# VCO_OUT_channel.net
KiCad netlist of a schematic drawn in Altium Designer
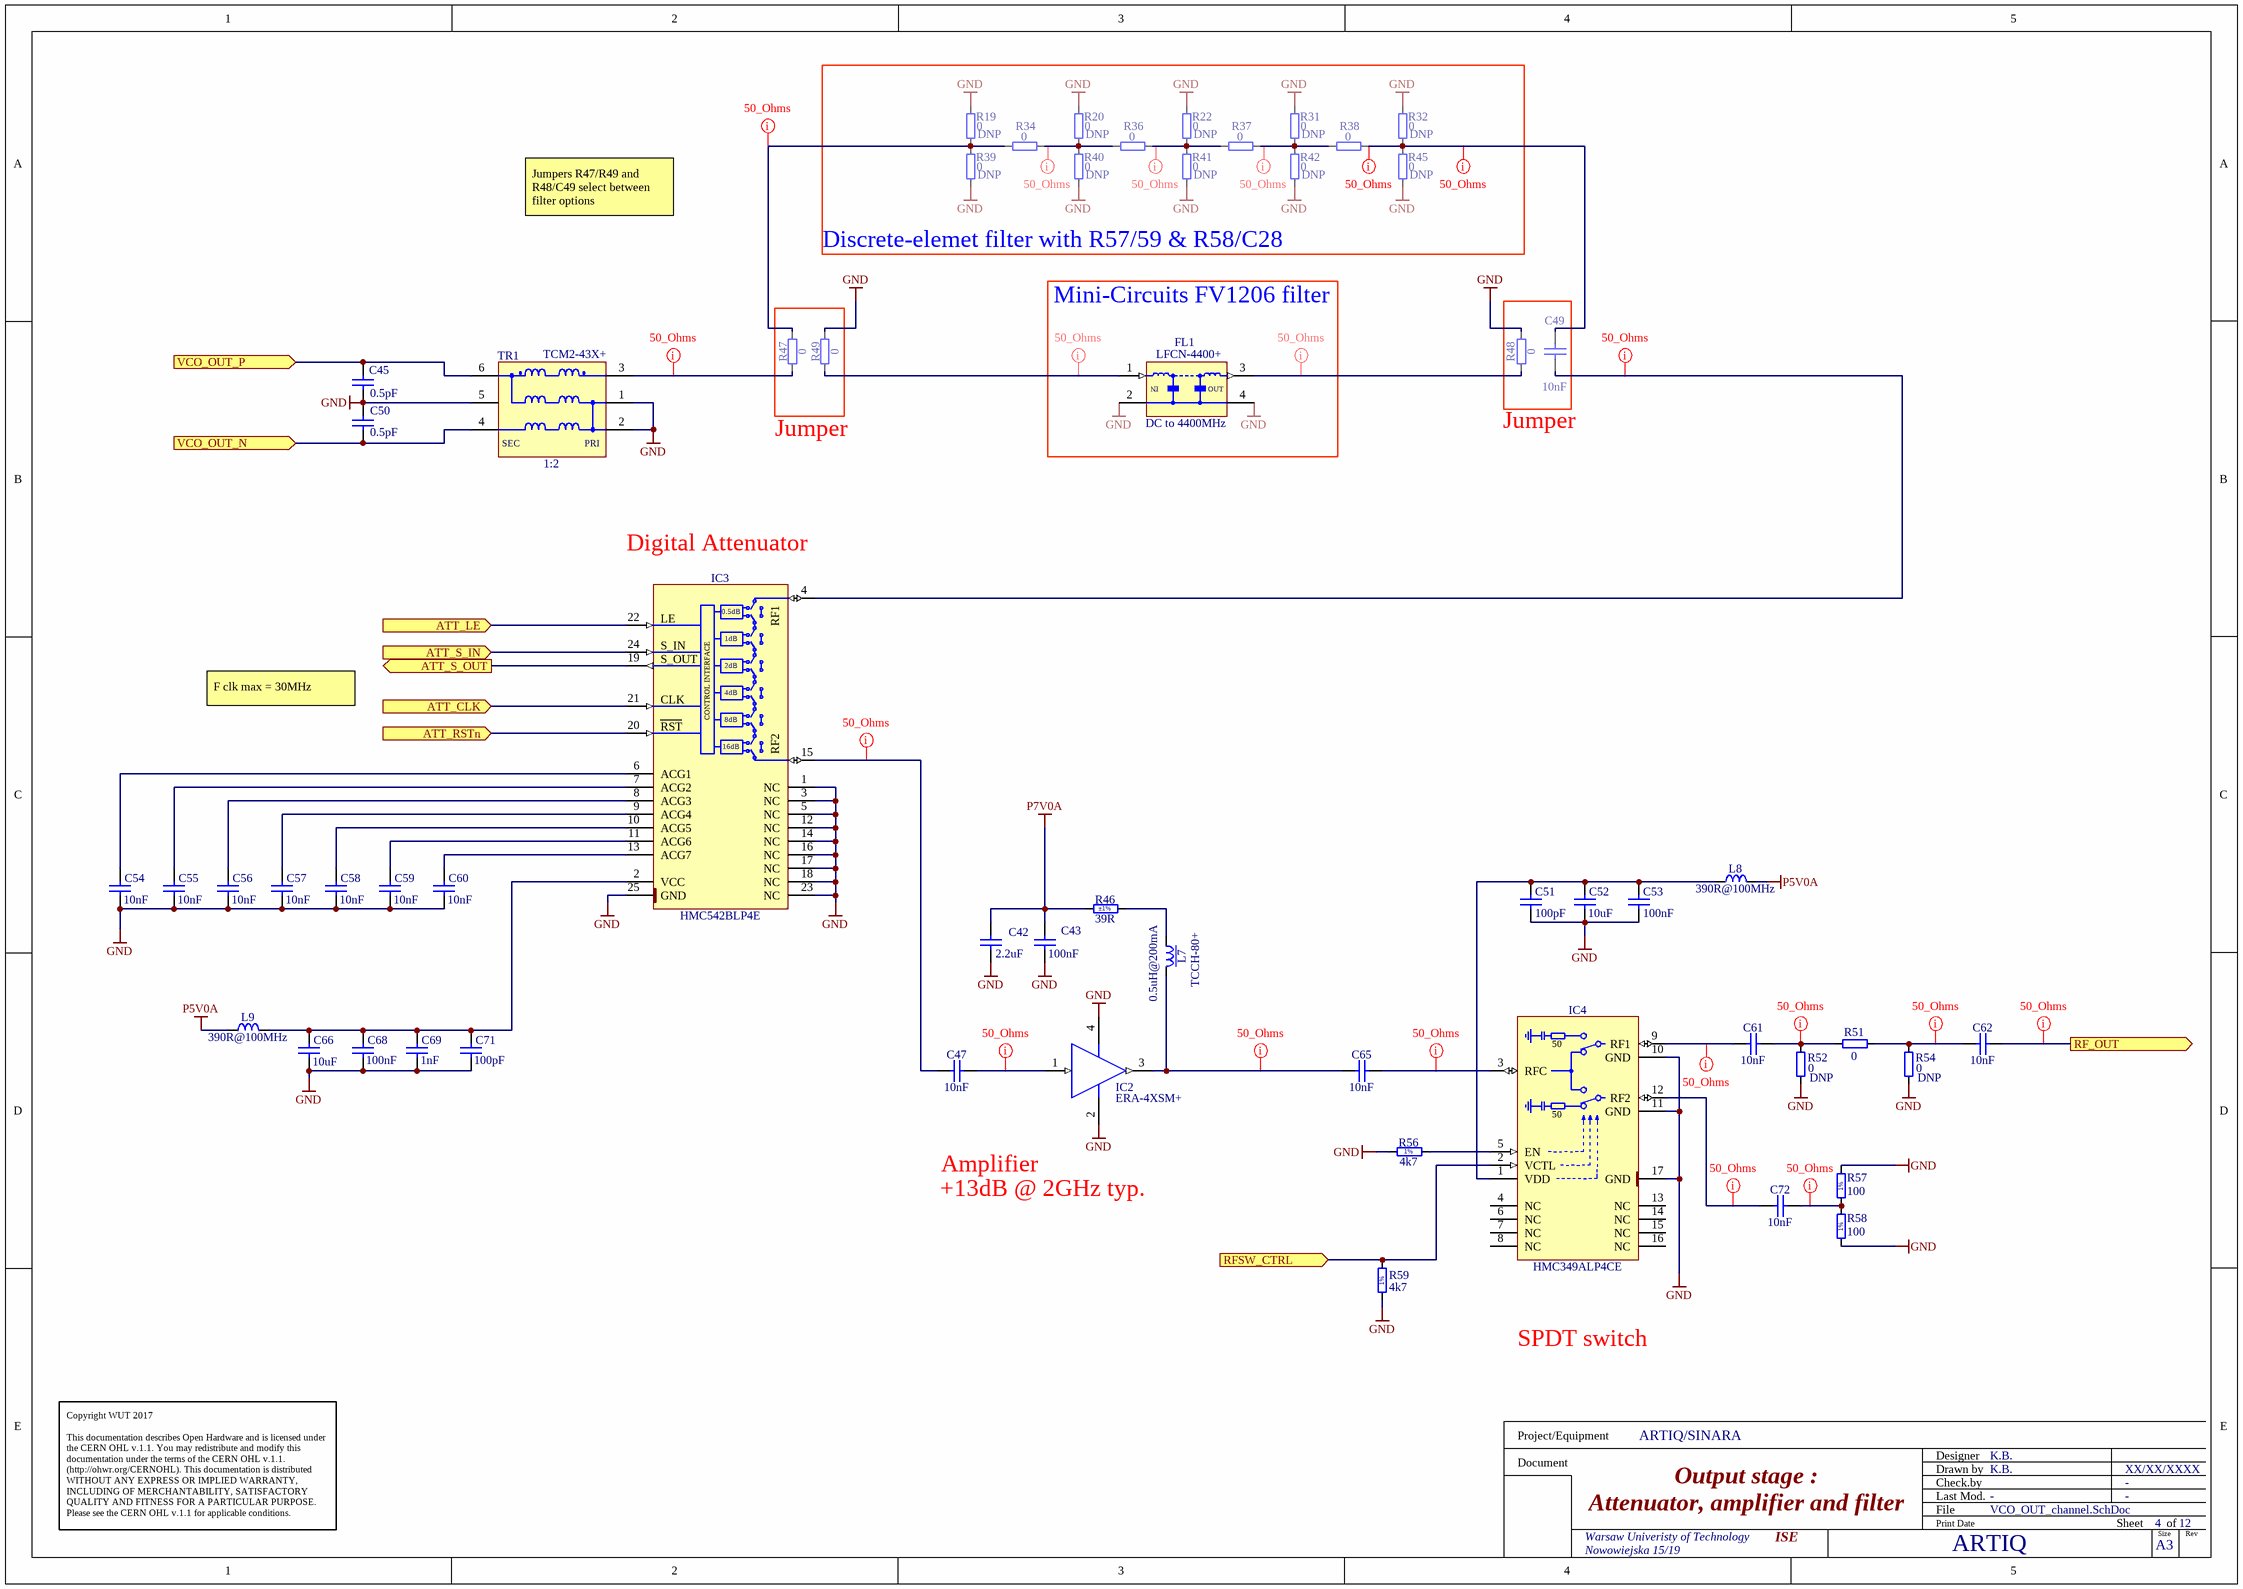
[diagram p0: VCO_OUT_channel.SchDoc]

(export (version "E")
  (design (tool "Eeschema 10.0.6"))
  (components
    (comp (ref "C42")
      (value "2.2uF")
      (footprint "CAPC2012X140N")
      (description "Non-polarised capacitor")
      (fields
        (field (name "PART NUMBER") "CC0805_2U2F_25V_20%_X7R")
        (field (name "VOLTAGE") "25V")
        (field (name "AUTHOR") "CERN DEM JLC")
      )
      (libsource (lib "Capacitors") (part "Capacitor - non polarized"))
    )
    (comp (ref "C43")
      (value "100nF")
      (footprint "CAPC1005X55N")
      (description "Non-polarised capacitor")
      (fields
        (field (name "PART NUMBER") "CC0402_100NF_16V_10%_X7R")
        (field (name "VOLTAGE") "16V")
        (field (name "AUTHOR") "CERN DEM JLC")
      )
      (libsource (lib "Capacitors") (part "Capacitor - non polarized"))
    )
    (comp (ref "C45")
      (value "0.5pF")
      (footprint "CAPC0402(1005)60_M")
      (description "CAP 0.5pF 10V ±0.1pF 0402 (1005 Metric) Thickness 0.6mm SMD")
      (fields (field (name "TOLERANCE") "Â±0.1pF"))
      (libsource (lib "Altium Content Vault") (part "CMP-1034-00013-1"))
    )
    (comp (ref "C47")
      (value "10nF")
      (footprint "CAPC1005X55N")
      (description "Non-polarised capacitor")
      (fields
        (field (name "PART NUMBER") "CC0402_10NF_16V_10%_X7R")
        (field (name "VOLTAGE") "16V")
        (field (name "AUTHOR") "CERN DEM JLC")
      )
      (libsource (lib "Capacitors") (part "Capacitor - non polarized"))
    )
    (comp (ref "C49")
      (value "10nF")
      (footprint "CAPC1005X55N")
      (description "Non-polarised capacitor")
      (fields
        (field (name "PART NUMBER") "CC0402_10NF_16V_10%_X7R")
        (field (name "VOLTAGE") "16V")
        (field (name "AUTHOR") "CERN DEM JLC")
      )
      (libsource (lib "Capacitors") (part "Capacitor - non polarized"))
    )
    (comp (ref "C50")
      (value "0.5pF")
      (footprint "CAPC0402(1005)60_M")
      (description "CAP 0.5pF 10V ±0.1pF 0402 (1005 Metric) Thickness 0.6mm SMD")
      (fields (field (name "TOLERANCE") "Â±0.1pF"))
      (libsource (lib "Altium Content Vault") (part "CMP-1034-00013-1"))
    )
    (comp (ref "C51")
      (value "100pF")
      (footprint "CAPC1005X55N")
      (description "Non-polarised capacitor")
      (fields
        (field (name "PART NUMBER") "CC0402_100PF_50V_5%_C0G")
        (field (name "VOLTAGE") "50V")
        (field (name "AUTHOR") "CERN DEM JLC")
      )
      (libsource (lib "Capacitors") (part "Capacitor - non polarized"))
    )
    (comp (ref "C52")
      (value "10uF")
      (footprint "CAPC1608X80N")
      (description "Non-polarised capacitor")
      (fields
        (field (name "PART NUMBER") "CC0603_10UF_16V_20%_X5R")
        (field (name "VOLTAGE") "16V")
        (field (name "AUTHOR") "CERN DEM MR")
      )
      (libsource (lib "Capacitors") (part "Capacitor - non polarized"))
    )
    (comp (ref "C53")
      (value "100nF")
      (footprint "CAPC1005X55N")
      (description "Non-polarised capacitor")
      (fields
        (field (name "PART NUMBER") "CC0402_100NF_16V_10%_X7R")
        (field (name "VOLTAGE") "16V")
        (field (name "AUTHOR") "CERN DEM JLC")
      )
      (libsource (lib "Capacitors") (part "Capacitor - non polarized"))
    )
    (comp (ref "C54")
      (value "10nF")
      (footprint "CAPC1005X55N")
      (description "Non-polarised capacitor")
      (fields
        (field (name "PART NUMBER") "CC0402_10NF_16V_10%_X7R")
        (field (name "VOLTAGE") "16V")
        (field (name "AUTHOR") "CERN DEM JLC")
      )
      (libsource (lib "Capacitors") (part "Capacitor - non polarized"))
    )
    (comp (ref "C55")
      (value "10nF")
      (footprint "CAPC1005X55N")
      (description "Non-polarised capacitor")
      (fields
        (field (name "PART NUMBER") "CC0402_10NF_16V_10%_X7R")
        (field (name "VOLTAGE") "16V")
        (field (name "AUTHOR") "CERN DEM JLC")
      )
      (libsource (lib "Capacitors") (part "Capacitor - non polarized"))
    )
    (comp (ref "C56")
      (value "10nF")
      (footprint "CAPC1005X55N")
      (description "Non-polarised capacitor")
      (fields
        (field (name "PART NUMBER") "CC0402_10NF_16V_10%_X7R")
        (field (name "VOLTAGE") "16V")
        (field (name "AUTHOR") "CERN DEM JLC")
      )
      (libsource (lib "Capacitors") (part "Capacitor - non polarized"))
    )
    (comp (ref "C57")
      (value "10nF")
      (footprint "CAPC1005X55N")
      (description "Non-polarised capacitor")
      (fields
        (field (name "PART NUMBER") "CC0402_10NF_16V_10%_X7R")
        (field (name "VOLTAGE") "16V")
        (field (name "AUTHOR") "CERN DEM JLC")
      )
      (libsource (lib "Capacitors") (part "Capacitor - non polarized"))
    )
    (comp (ref "C58")
      (value "10nF")
      (footprint "CAPC1005X55N")
      (description "Non-polarised capacitor")
      (fields
        (field (name "PART NUMBER") "CC0402_10NF_16V_10%_X7R")
        (field (name "VOLTAGE") "16V")
        (field (name "AUTHOR") "CERN DEM JLC")
      )
      (libsource (lib "Capacitors") (part "Capacitor - non polarized"))
    )
    (comp (ref "C59")
      (value "10nF")
      (footprint "CAPC1005X55N")
      (description "Non-polarised capacitor")
      (fields
        (field (name "PART NUMBER") "CC0402_10NF_16V_10%_X7R")
        (field (name "VOLTAGE") "16V")
        (field (name "AUTHOR") "CERN DEM JLC")
      )
      (libsource (lib "Capacitors") (part "Capacitor - non polarized"))
    )
    (comp (ref "C60")
      (value "10nF")
      (footprint "CAPC1005X55N")
      (description "Non-polarised capacitor")
      (fields
        (field (name "PART NUMBER") "CC0402_10NF_16V_10%_X7R")
        (field (name "VOLTAGE") "16V")
        (field (name "AUTHOR") "CERN DEM JLC")
      )
      (libsource (lib "Capacitors") (part "Capacitor - non polarized"))
    )
    (comp (ref "C61")
      (value "10nF")
      (footprint "CAPC1005X55N")
      (description "Non-polarised capacitor")
      (fields
        (field (name "PART NUMBER") "CC0402_10NF_16V_10%_X7R")
        (field (name "VOLTAGE") "16V")
        (field (name "AUTHOR") "CERN DEM JLC")
      )
      (libsource (lib "Capacitors") (part "Capacitor - non polarized"))
    )
    (comp (ref "C62")
      (value "10nF")
      (footprint "CAPC1005X55N")
      (description "Non-polarised capacitor")
      (fields
        (field (name "PART NUMBER") "CC0402_10NF_16V_10%_X7R")
        (field (name "VOLTAGE") "16V")
        (field (name "AUTHOR") "CERN DEM JLC")
      )
      (libsource (lib "Capacitors") (part "Capacitor - non polarized"))
    )
    (comp (ref "C65")
      (value "10nF")
      (footprint "CAPC1005X55N")
      (description "Non-polarised capacitor")
      (fields
        (field (name "PART NUMBER") "CC0402_10NF_16V_10%_X7R")
        (field (name "VOLTAGE") "16V")
        (field (name "AUTHOR") "CERN DEM JLC")
      )
      (libsource (lib "Capacitors") (part "Capacitor - non polarized"))
    )
    (comp (ref "C66")
      (value "10uF")
      (footprint "CAPC1608X80N")
      (description "Non-polarised capacitor")
      (fields
        (field (name "PART NUMBER") "CC0603_10UF_16V_20%_X5R")
        (field (name "VOLTAGE") "16V")
        (field (name "AUTHOR") "CERN DEM MR")
      )
      (libsource (lib "Capacitors") (part "Capacitor - non polarized"))
    )
    (comp (ref "C68")
      (value "100nF")
      (footprint "CAPC1005X55N")
      (description "Non-polarised capacitor")
      (fields
        (field (name "PART NUMBER") "CC0402_100NF_16V_10%_X7R")
        (field (name "VOLTAGE") "16V")
        (field (name "AUTHOR") "CERN DEM JLC")
      )
      (libsource (lib "Capacitors") (part "Capacitor - non polarized"))
    )
    (comp (ref "C69")
      (value "1nF")
      (footprint "CAPC1005X55N")
      (description "Non-polarised capacitor")
      (fields
        (field (name "PART NUMBER") "CC0402_1NF_50V_10%_X7R")
        (field (name "VOLTAGE") "50V")
        (field (name "AUTHOR") "CERN DEM JLC")
      )
      (libsource (lib "Capacitors") (part "Capacitor - non polarized"))
    )
    (comp (ref "C71")
      (value "100pF")
      (footprint "CAPC1005X55N")
      (description "Non-polarised capacitor")
      (fields
        (field (name "PART NUMBER") "CC0402_100PF_50V_5%_C0G")
        (field (name "VOLTAGE") "50V")
        (field (name "AUTHOR") "CERN DEM JLC")
      )
      (libsource (lib "Capacitors") (part "Capacitor - non polarized"))
    )
    (comp (ref "C72")
      (value "10nF")
      (footprint "CAPC1005X55N")
      (description "Non-polarised capacitor")
      (fields
        (field (name "PART NUMBER") "CC0402_10NF_16V_10%_X7R")
        (field (name "VOLTAGE") "16V")
        (field (name "AUTHOR") "CERN DEM JLC")
      )
      (libsource (lib "Capacitors") (part "Capacitor - non polarized"))
    )
    (comp (ref "FL1")
      (value "DC to 4400MHz")
      (footprint "FIL_MINI-CIRCUITS_FV1206")
      (description "50 Ohm DC to 4400MHz Low Pass Filter")
      (fields
        (field (name "PART NUMBER") "FIL_MINI-CIRCUITS_LFCN-4400+")
        (field (name "MANUFACTURER") "MINI-CIRCUITS")
        (field (name "MANUFACTURER PART NUMBER") "LFCN-4400+")
        (field (name "AUTHOR") "CERN DEM JLC")
      )
      (libsource (lib "LIBRARY_SCH") (part "FIL_MINI-CIRCUITS_LFCN-320"))
    )
    (comp (ref "IC2")
      (value "ERA-4XSM+")
      (footprint "MINI-CIRCUITS_WW107")
      (description "DC-4GHz Monolithic Amplifier")
      (fields (field (name "MANUFACTURER") "MINI-CIRCUITS") (field (name "AUTHOR") "CERN DEM JMW"))
      (libsource (lib "ICs And Semiconductors") (part "ERA-4XSM+"))
    )
    (comp (ref "IC3")
      (value "HMC542BLP4E")
      (footprint "QFN50P400X400X100-25N-S295")
      (description "0.5dB LSB GaAs MMIC 6-bit Digital Serial Control Attenuator, DC - 4GHz")
      (fields (field (name "MANUFACTURER") "HITTITE MICROWAVE CORP") (field (name "AUTHOR") "CERN DEM JMW"))
      (libsource (lib "ICs And Semiconductors") (part "HMC542BLP4E"))
    )
    (comp (ref "IC4")
      (value "HMC349ALP4CE")
      (footprint "QFN65P400X400X100-17N-S255")
      (description "DC-4GHz High Isolation SPDT Non-Reflective Switch")
      (fields (field (name "MANUFACTURER") "ANALOG DEVICES") (field (name "AUTHOR") "CERN DEM JLC"))
      (libsource (lib "ICs And Semiconductors") (part "HMC349ALP4CE"))
    )
    (comp (ref "L7")
      (value "0.5uH@200mA")
      (footprint "IND_MINI-CIRCUITS_GU1604")
      (description "50 Ohms, 50 to 8200 MHz RF Choke")
      (fields
        (field (name "PART NUMBER") "IND_MINI-CIRCUITS_TCCH-80+")
        (field (name "POWER") "200mA")
        (field (name "MANUFACTURER PART NUMBER") "TCCH-80+")
        (field (name "AUTHOR") "CERN DEM JLC")
      )
      (libsource (lib "Inductors & Transformers") (part "IND_MINI-CIRCUITS_TCCH-80+"))
    )
    (comp (ref "L8")
      (value "390R@100MHz")
      (footprint "INDC1608X95N")
      (description "Inductor")
      (fields
        (field (name "PART NUMBER") "IND0603_TDK_MPZ1608R391A")
        (field (name "POWER") "1.2A")
        (field (name "AUTHOR") "CERN DEM JLC")
      )
      (libsource (lib "Inductors & Transformers") (part "Inductor"))
    )
    (comp (ref "L9")
      (value "390R@100MHz")
      (footprint "INDC1608X95N")
      (description "Inductor")
      (fields
        (field (name "PART NUMBER") "IND0603_TDK_MPZ1608R391A")
        (field (name "POWER") "1.2A")
        (field (name "AUTHOR") "CERN DEM JLC")
      )
      (libsource (lib "Inductors & Transformers") (part "Inductor"))
    )
    (comp (ref "R19")
      (value "0")
      (footprint "RESC1005X40N")
      (description "Resistor")
      (fields
        (field (name "PART NUMBER") "R0402_0R_JUMPER")
        (field (name "MANUFACTURER") "GENERIC")
        (field (name "MOUNTED") "DNP")
        (field (name "AUTHOR") "CERN DEM JLC")
      )
      (libsource (lib "Resistors") (part "Resistor"))
    )
    (comp (ref "R20")
      (value "0")
      (footprint "RESC1005X40N")
      (description "Resistor")
      (fields
        (field (name "PART NUMBER") "R0402_0R_JUMPER")
        (field (name "MANUFACTURER") "GENERIC")
        (field (name "MOUNTED") "DNP")
        (field (name "AUTHOR") "CERN DEM JLC")
      )
      (libsource (lib "Resistors") (part "Resistor"))
    )
    (comp (ref "R22")
      (value "0")
      (footprint "RESC1005X40N")
      (description "Resistor")
      (fields
        (field (name "PART NUMBER") "R0402_0R_JUMPER")
        (field (name "MANUFACTURER") "GENERIC")
        (field (name "MOUNTED") "DNP")
        (field (name "AUTHOR") "CERN DEM JLC")
      )
      (libsource (lib "Resistors") (part "Resistor"))
    )
    (comp (ref "R31")
      (value "0")
      (footprint "RESC1005X40N")
      (description "Resistor")
      (fields
        (field (name "PART NUMBER") "R0402_0R_JUMPER")
        (field (name "MANUFACTURER") "GENERIC")
        (field (name "MOUNTED") "DNP")
        (field (name "AUTHOR") "CERN DEM JLC")
      )
      (libsource (lib "Resistors") (part "Resistor"))
    )
    (comp (ref "R32")
      (value "0")
      (footprint "RESC1005X40N")
      (description "Resistor")
      (fields
        (field (name "PART NUMBER") "R0402_0R_JUMPER")
        (field (name "MANUFACTURER") "GENERIC")
        (field (name "MOUNTED") "DNP")
        (field (name "AUTHOR") "CERN DEM JLC")
      )
      (libsource (lib "Resistors") (part "Resistor"))
    )
    (comp (ref "R34")
      (value "0")
      (footprint "RESC1005X40N")
      (description "Resistor")
      (fields
        (field (name "PART NUMBER") "R0402_0R_JUMPER")
        (field (name "MANUFACTURER") "GENERIC")
        (field (name "AUTHOR") "CERN DEM JLC")
      )
      (libsource (lib "Resistors") (part "Resistor"))
    )
    (comp (ref "R36")
      (value "0")
      (footprint "RESC1005X40N")
      (description "Resistor")
      (fields
        (field (name "PART NUMBER") "R0402_0R_JUMPER")
        (field (name "MANUFACTURER") "GENERIC")
        (field (name "AUTHOR") "CERN DEM JLC")
      )
      (libsource (lib "Resistors") (part "Resistor"))
    )
    (comp (ref "R37")
      (value "0")
      (footprint "RESC1005X40N")
      (description "Resistor")
      (fields
        (field (name "PART NUMBER") "R0402_0R_JUMPER")
        (field (name "MANUFACTURER") "GENERIC")
        (field (name "AUTHOR") "CERN DEM JLC")
      )
      (libsource (lib "Resistors") (part "Resistor"))
    )
    (comp (ref "R38")
      (value "0")
      (footprint "RESC1005X40N")
      (description "Resistor")
      (fields
        (field (name "PART NUMBER") "R0402_0R_JUMPER")
        (field (name "MANUFACTURER") "GENERIC")
        (field (name "AUTHOR") "CERN DEM JLC")
      )
      (libsource (lib "Resistors") (part "Resistor"))
    )
    (comp (ref "R39")
      (value "0")
      (footprint "RESC1005X40N")
      (description "Resistor")
      (fields
        (field (name "PART NUMBER") "R0402_0R_JUMPER")
        (field (name "MANUFACTURER") "GENERIC")
        (field (name "MOUNTED") "DNP")
        (field (name "AUTHOR") "CERN DEM JLC")
      )
      (libsource (lib "Resistors") (part "Resistor"))
    )
    (comp (ref "R40")
      (value "0")
      (footprint "RESC1005X40N")
      (description "Resistor")
      (fields
        (field (name "PART NUMBER") "R0402_0R_JUMPER")
        (field (name "MANUFACTURER") "GENERIC")
        (field (name "MOUNTED") "DNP")
        (field (name "AUTHOR") "CERN DEM JLC")
      )
      (libsource (lib "Resistors") (part "Resistor"))
    )
    (comp (ref "R41")
      (value "0")
      (footprint "RESC1005X40N")
      (description "Resistor")
      (fields
        (field (name "PART NUMBER") "R0402_0R_JUMPER")
        (field (name "MANUFACTURER") "GENERIC")
        (field (name "MOUNTED") "DNP")
        (field (name "AUTHOR") "CERN DEM JLC")
      )
      (libsource (lib "Resistors") (part "Resistor"))
    )
    (comp (ref "R42")
      (value "0")
      (footprint "RESC1005X40N")
      (description "Resistor")
      (fields
        (field (name "PART NUMBER") "R0402_0R_JUMPER")
        (field (name "MANUFACTURER") "GENERIC")
        (field (name "MOUNTED") "DNP")
        (field (name "AUTHOR") "CERN DEM JLC")
      )
      (libsource (lib "Resistors") (part "Resistor"))
    )
    (comp (ref "R45")
      (value "0")
      (footprint "RESC1005X40N")
      (description "Resistor")
      (fields
        (field (name "PART NUMBER") "R0402_0R_JUMPER")
        (field (name "MANUFACTURER") "GENERIC")
        (field (name "MOUNTED") "DNP")
        (field (name "AUTHOR") "CERN DEM JLC")
      )
      (libsource (lib "Resistors") (part "Resistor"))
    )
    (comp (ref "R46")
      (value "39R")
      (footprint "RESC3225X70N")
      (description "Resistor - 1%")
      (fields
        (field (name "PART NUMBER") "R1210_39R_1%_0.5W_100PPM")
        (field (name "POWER") "0.5W")
        (field (name "TOLERANCE") "±1%")
        (field (name "AUTHOR") "GK")
      )
      (libsource (lib "Passives_RC") (part "R1210_39R_1%_0.5W_100PPM"))
    )
    (comp (ref "R47")
      (value "0")
      (footprint "RESC1005X40N")
      (description "Resistor")
      (fields
        (field (name "PART NUMBER") "R0402_0R_JUMPER")
        (field (name "MANUFACTURER") "GENERIC")
        (field (name "AUTHOR") "CERN DEM JLC")
      )
      (libsource (lib "Resistors") (part "Resistor"))
    )
    (comp (ref "R48")
      (value "0")
      (footprint "RESC1005X40N")
      (description "Resistor")
      (fields
        (field (name "PART NUMBER") "R0402_0R_JUMPER")
        (field (name "MANUFACTURER") "GENERIC")
        (field (name "AUTHOR") "CERN DEM JLC")
      )
      (libsource (lib "Resistors") (part "Resistor"))
    )
    (comp (ref "R49")
      (value "0")
      (footprint "RESC1005X40N")
      (description "Resistor")
      (fields
        (field (name "PART NUMBER") "R0402_0R_JUMPER")
        (field (name "MANUFACTURER") "GENERIC")
        (field (name "AUTHOR") "CERN DEM JLC")
      )
      (libsource (lib "Resistors") (part "Resistor"))
    )
    (comp (ref "R51")
      (value "0")
      (footprint "RESC1005X40N")
      (description "Resistor")
      (fields
        (field (name "PART NUMBER") "R0402_0R_JUMPER")
        (field (name "MANUFACTURER") "GENERIC")
        (field (name "AUTHOR") "CERN DEM JLC")
      )
      (libsource (lib "Resistors") (part "Resistor"))
    )
    (comp (ref "R52")
      (value "0")
      (footprint "RESC1005X40N")
      (description "Resistor")
      (fields
        (field (name "PART NUMBER") "R0402_0R_JUMPER")
        (field (name "MANUFACTURER") "GENERIC")
        (field (name "MOUNTED") "DNP")
        (field (name "AUTHOR") "CERN DEM JLC")
      )
      (libsource (lib "Resistors") (part "Resistor"))
    )
    (comp (ref "R54")
      (value "0")
      (footprint "RESC1005X40N")
      (description "Resistor")
      (fields
        (field (name "PART NUMBER") "R0402_0R_JUMPER")
        (field (name "MANUFACTURER") "GENERIC")
        (field (name "MOUNTED") "DNP")
        (field (name "AUTHOR") "CERN DEM JLC")
      )
      (libsource (lib "Resistors") (part "Resistor"))
    )
    (comp (ref "R56")
      (value "4k7")
      (footprint "RESC1005X40N")
      (description "Resistor - 1%")
      (fields
        (field (name "PART NUMBER") "R0402_4K7_1%_0.0625W_100PPM")
        (field (name "POWER") "0.0625W")
        (field (name "AUTHOR") "CERN DEM JLC")
      )
      (libsource (lib "Resistors") (part "Resistor - 1%"))
    )
    (comp (ref "R57")
      (value "100")
      (footprint "RESC1005X40N")
      (description "Resistor - 1%")
      (fields
        (field (name "PART NUMBER") "R0402_100R_1%_0.1W_100PPM")
        (field (name "POWER") "0.1W")
        (field (name "AUTHOR") "CERN DEM JLC")
      )
      (libsource (lib "Resistors") (part "Resistor - 1%"))
    )
    (comp (ref "R58")
      (value "100")
      (footprint "RESC1005X40N")
      (description "Resistor - 1%")
      (fields
        (field (name "PART NUMBER") "R0402_100R_1%_0.1W_100PPM")
        (field (name "POWER") "0.1W")
        (field (name "AUTHOR") "CERN DEM JLC")
      )
      (libsource (lib "Resistors") (part "Resistor - 1%"))
    )
    (comp (ref "R59")
      (value "4k7")
      (footprint "RESC1005X40N")
      (description "Resistor - 1%")
      (fields
        (field (name "PART NUMBER") "R0402_4K7_1%_0.0625W_100PPM")
        (field (name "POWER") "0.0625W")
        (field (name "AUTHOR") "CERN DEM JLC")
      )
      (libsource (lib "Resistors") (part "Resistor - 1%"))
    )
    (comp (ref "TR1")
      (value "1:2")
      (footprint "XFMR_MINI-CIRCUITS_DB1627")
      (description "50 OHMS 10 to 4000 MHz RF Transformer")
      (fields
        (field (name "PART NUMBER") "XFMR_MINI-CIRCUITS_TCM2-43X+")
        (field (name "POWER") "0.4W")
        (field (name "MANUFACTURER PART NUMBER") "TCM2-43X+")
        (field (name "AUTHOR") "CERN DEM BC")
      )
      (libsource (lib "Inductors & Transformers") (part "XFMR_MINI-CIRCUITS_TCM2-43X"))
    )
  )
  (nets
    (net (code "1") (name "/ATT_CLK") (class "Default")
      (node (ref "IC3") (pin "21") (pinfunction "SHIFT_CLOCK_21") (pintype "input"))
    )
    (net (code "2") (name "/ATT_LE") (class "Default")
      (node (ref "IC3") (pin "22") (pinfunction "LATCH_ENABLE_22") (pintype "input"))
    )
    (net (code "3") (name "/ATT_RSTn") (class "Default")
      (node (ref "IC3") (pin "20") (pinfunction "~{RESET}_20") (pintype "input"))
    )
    (net (code "4") (name "/ATT_S_IN") (class "Default")
      (node (ref "IC3") (pin "24") (pinfunction "SERIAL_INPUT_24") (pintype "input"))
    )
    (net (code "5") (name "/ATT_S_OUT") (class "Default")
      (node (ref "IC3") (pin "19") (pinfunction "SERIAL_OUTPUT_19") (pintype "output"))
    )
    (net (code "6") (name "/RFSW_CTRL") (class "Default")
      (node (ref "IC4") (pin "2") (pinfunction "VCTL_2") (pintype "input"))
      (node (ref "R59") (pin "2") (pinfunction "2_2") (pintype "passive"))
    )
    (net (code "7") (name "/RF_OUT") (class "Default")
      (node (ref "C62") (pin "2") (pinfunction "2_2") (pintype "passive"))
    )
    (net (code "8") (name "/VCO_OUT_N") (class "Default")
      (node (ref "C50") (pin "1") (pinfunction "1_1") (pintype "passive"))
      (node (ref "TR1") (pin "4") (pinfunction "S1_4") (pintype "passive"))
    )
    (net (code "9") (name "/VCO_OUT_P") (class "Default")
      (node (ref "C45") (pin "2") (pinfunction "2_2") (pintype "passive"))
      (node (ref "TR1") (pin "6") (pinfunction "S1_6") (pintype "passive"))
    )
    (net (code "10") (name "GND") (class "Default")
      (node (ref "C42") (pin "1") (pinfunction "1_1") (pintype "passive"))
      (node (ref "C43") (pin "1") (pinfunction "1_1") (pintype "passive"))
      (node (ref "C45") (pin "1") (pinfunction "1_1") (pintype "passive"))
      (node (ref "C50") (pin "2") (pinfunction "2_2") (pintype "passive"))
      (node (ref "C51") (pin "2") (pinfunction "2_2") (pintype "passive"))
      (node (ref "C52") (pin "1") (pinfunction "1_1") (pintype "passive"))
      (node (ref "C53") (pin "1") (pinfunction "1_1") (pintype "passive"))
      (node (ref "C54") (pin "1") (pinfunction "1_1") (pintype "passive"))
      (node (ref "C55") (pin "1") (pinfunction "1_1") (pintype "passive"))
      (node (ref "C56") (pin "1") (pinfunction "1_1") (pintype "passive"))
      (node (ref "C57") (pin "1") (pinfunction "1_1") (pintype "passive"))
      (node (ref "C58") (pin "1") (pinfunction "1_1") (pintype "passive"))
      (node (ref "C59") (pin "1") (pinfunction "1_1") (pintype "passive"))
      (node (ref "C60") (pin "1") (pinfunction "1_1") (pintype "passive"))
      (node (ref "C66") (pin "1") (pinfunction "1_1") (pintype "passive"))
      (node (ref "C68") (pin "1") (pinfunction "1_1") (pintype "passive"))
      (node (ref "C69") (pin "1") (pinfunction "1_1") (pintype "passive"))
      (node (ref "C71") (pin "1") (pinfunction "1_1") (pintype "passive"))
      (node (ref "FL1") (pin "2") (pinfunction "GND_2") (pintype "power_in"))
      (node (ref "FL1") (pin "4") (pinfunction "GND_4") (pintype "power_in"))
      (node (ref "IC2") (pin "2") (pinfunction "GND_2") (pintype "power_in"))
      (node (ref "IC2") (pin "4") (pinfunction "GND_4") (pintype "power_in"))
      (node (ref "IC3") (pin "1") (pinfunction "NC_1") (pintype "passive"))
      (node (ref "IC3") (pin "12") (pinfunction "NC_12") (pintype "passive"))
      (node (ref "IC3") (pin "14") (pinfunction "NC_14") (pintype "passive"))
      (node (ref "IC3") (pin "16") (pinfunction "NC_16") (pintype "passive"))
      (node (ref "IC3") (pin "17") (pinfunction "NC_17") (pintype "passive"))
      (node (ref "IC3") (pin "18") (pinfunction "NC_18") (pintype "passive"))
      (node (ref "IC3") (pin "23") (pinfunction "NC_23") (pintype "passive"))
      (node (ref "IC3") (pin "25") (pinfunction "GND_25") (pintype "power_in"))
      (node (ref "IC3") (pin "3") (pinfunction "NC_3") (pintype "passive"))
      (node (ref "IC3") (pin "5") (pinfunction "NC_5") (pintype "passive"))
      (node (ref "IC4") (pin "10") (pinfunction "GND_10") (pintype "power_in"))
      (node (ref "IC4") (pin "11") (pinfunction "GND_11") (pintype "power_in"))
      (node (ref "IC4") (pin "17") (pinfunction "GND_17") (pintype "power_in"))
      (node (ref "R19") (pin "1") (pinfunction "1_1") (pintype "passive"))
      (node (ref "R20") (pin "1") (pinfunction "1_1") (pintype "passive"))
      (node (ref "R22") (pin "1") (pinfunction "1_1") (pintype "passive"))
      (node (ref "R31") (pin "1") (pinfunction "1_1") (pintype "passive"))
      (node (ref "R32") (pin "1") (pinfunction "1_1") (pintype "passive"))
      (node (ref "R39") (pin "1") (pinfunction "1_1") (pintype "passive"))
      (node (ref "R40") (pin "1") (pinfunction "1_1") (pintype "passive"))
      (node (ref "R41") (pin "1") (pinfunction "1_1") (pintype "passive"))
      (node (ref "R42") (pin "1") (pinfunction "1_1") (pintype "passive"))
      (node (ref "R45") (pin "1") (pinfunction "1_1") (pintype "passive"))
      (node (ref "R48") (pin "1") (pinfunction "1_1") (pintype "passive"))
      (node (ref "R49") (pin "2") (pinfunction "2_2") (pintype "passive"))
      (node (ref "R52") (pin "1") (pinfunction "1_1") (pintype "passive"))
      (node (ref "R54") (pin "1") (pinfunction "1_1") (pintype "passive"))
      (node (ref "R56") (pin "1") (pinfunction "1_1") (pintype "passive"))
      (node (ref "R57") (pin "2") (pinfunction "2_2") (pintype "passive"))
      (node (ref "R58") (pin "1") (pinfunction "1_1") (pintype "passive"))
      (node (ref "R59") (pin "1") (pinfunction "1_1") (pintype "passive"))
      (node (ref "TR1") (pin "1") (pinfunction "P1_1") (pintype "passive"))
      (node (ref "TR1") (pin "2") (pinfunction "P1_2") (pintype "passive"))
      (node (ref "TR1") (pin "5") (pinfunction "NC_5") (pintype "passive"))
    )
    (net (code "11") (name "Net-(C49-Pad2)") (class "Default")
      (node (ref "C49") (pin "2") (pinfunction "2_2") (pintype "passive"))
      (node (ref "R32") (pin "2") (pinfunction "2_2") (pintype "passive"))
      (node (ref "R38") (pin "1") (pinfunction "1_1") (pintype "passive"))
      (node (ref "R45") (pin "2") (pinfunction "2_2") (pintype "passive"))
    )
    (net (code "12") (name "Net-(C61-Pad2)") (class "Default")
      (node (ref "C61") (pin "2") (pinfunction "2_2") (pintype "passive"))
      (node (ref "R51") (pin "1") (pinfunction "1_1") (pintype "passive"))
      (node (ref "R52") (pin "2") (pinfunction "2_2") (pintype "passive"))
    )
    (net (code "13") (name "Net-(C62-Pad1)") (class "Default")
      (node (ref "C62") (pin "1") (pinfunction "1_1") (pintype "passive"))
      (node (ref "R51") (pin "2") (pinfunction "2_2") (pintype "passive"))
      (node (ref "R54") (pin "2") (pinfunction "2_2") (pintype "passive"))
    )
    (net (code "14") (name "Net-(C72-Pad2)") (class "Default")
      (node (ref "C72") (pin "2") (pinfunction "2_2") (pintype "passive"))
      (node (ref "R57") (pin "1") (pinfunction "1_1") (pintype "passive"))
      (node (ref "R58") (pin "2") (pinfunction "2_2") (pintype "passive"))
    )
    (net (code "15") (name "Net-(FL1-RFIN)") (class "Default")
      (node (ref "FL1") (pin "1") (pinfunction "RFIN_1") (pintype "input"))
      (node (ref "R49") (pin "1") (pinfunction "1_1") (pintype "passive"))
    )
    (net (code "16") (name "Net-(FL1-RFOUT)") (class "Default")
      (node (ref "FL1") (pin "3") (pinfunction "RFOUT_3") (pintype "output"))
      (node (ref "R48") (pin "2") (pinfunction "2_2") (pintype "passive"))
    )
    (net (code "17") (name "Net-(IC2-RF_IN)") (class "Default")
      (node (ref "C47") (pin "2") (pinfunction "2_2") (pintype "passive"))
      (node (ref "IC2") (pin "1") (pinfunction "RF_IN_1") (pintype "input"))
    )
    (net (code "18") (name "Net-(IC2-RF_OUT)") (class "Default")
      (node (ref "C65") (pin "1") (pinfunction "1_1") (pintype "passive"))
      (node (ref "IC2") (pin "3") (pinfunction "RF_OUT_3") (pintype "output"))
      (node (ref "L7") (pin "3") (pinfunction "3_3") (pintype "passive"))
    )
    (net (code "19") (name "Net-(IC3-ACG1)") (class "Default")
      (node (ref "C54") (pin "2") (pinfunction "2_2") (pintype "passive"))
      (node (ref "IC3") (pin "6") (pinfunction "ACG1_6") (pintype "passive"))
    )
    (net (code "20") (name "Net-(IC3-ACG2)") (class "Default")
      (node (ref "C55") (pin "2") (pinfunction "2_2") (pintype "passive"))
      (node (ref "IC3") (pin "7") (pinfunction "ACG2_7") (pintype "passive"))
    )
    (net (code "21") (name "Net-(IC3-ACG3)") (class "Default")
      (node (ref "C56") (pin "2") (pinfunction "2_2") (pintype "passive"))
      (node (ref "IC3") (pin "8") (pinfunction "ACG3_8") (pintype "passive"))
    )
    (net (code "22") (name "Net-(IC3-ACG4)") (class "Default")
      (node (ref "C57") (pin "2") (pinfunction "2_2") (pintype "passive"))
      (node (ref "IC3") (pin "9") (pinfunction "ACG4_9") (pintype "passive"))
    )
    (net (code "23") (name "Net-(IC3-ACG5)") (class "Default")
      (node (ref "C58") (pin "2") (pinfunction "2_2") (pintype "passive"))
      (node (ref "IC3") (pin "10") (pinfunction "ACG5_10") (pintype "passive"))
    )
    (net (code "24") (name "Net-(IC3-ACG6)") (class "Default")
      (node (ref "C59") (pin "2") (pinfunction "2_2") (pintype "passive"))
      (node (ref "IC3") (pin "11") (pinfunction "ACG6_11") (pintype "passive"))
    )
    (net (code "25") (name "Net-(IC3-ACG7)") (class "Default")
      (node (ref "C60") (pin "2") (pinfunction "2_2") (pintype "passive"))
      (node (ref "IC3") (pin "13") (pinfunction "ACG7_13") (pintype "passive"))
    )
    (net (code "26") (name "Net-(IC3-RF1)") (class "Default")
      (node (ref "C49") (pin "1") (pinfunction "1_1") (pintype "passive"))
      (node (ref "IC3") (pin "4") (pinfunction "RF1_4") (pintype "bidirectional"))
    )
    (net (code "27") (name "Net-(IC3-RF2)") (class "Default")
      (node (ref "C47") (pin "1") (pinfunction "1_1") (pintype "passive"))
      (node (ref "IC3") (pin "15") (pinfunction "RF2_15") (pintype "bidirectional"))
    )
    (net (code "28") (name "Net-(IC3-VCC)") (class "Default")
      (node (ref "C66") (pin "2") (pinfunction "2_2") (pintype "passive"))
      (node (ref "C68") (pin "2") (pinfunction "2_2") (pintype "passive"))
      (node (ref "C69") (pin "2") (pinfunction "2_2") (pintype "passive"))
      (node (ref "C71") (pin "2") (pinfunction "2_2") (pintype "passive"))
      (node (ref "IC3") (pin "2") (pinfunction "VCC_2") (pintype "power_in"))
      (node (ref "L9") (pin "2") (pinfunction "2_2") (pintype "passive"))
    )
    (net (code "29") (name "Net-(IC4-EN)") (class "Default")
      (node (ref "IC4") (pin "5") (pinfunction "EN_5") (pintype "input"))
      (node (ref "R56") (pin "2") (pinfunction "2_2") (pintype "passive"))
    )
    (net (code "30") (name "Net-(IC4-RF1)") (class "Default")
      (node (ref "C61") (pin "1") (pinfunction "1_1") (pintype "passive"))
      (node (ref "IC4") (pin "9") (pinfunction "RF1_9") (pintype "bidirectional"))
    )
    (net (code "31") (name "Net-(IC4-RF2)") (class "Default")
      (node (ref "C72") (pin "1") (pinfunction "1_1") (pintype "passive"))
      (node (ref "IC4") (pin "12") (pinfunction "RF2_12") (pintype "bidirectional"))
    )
    (net (code "32") (name "Net-(IC4-RFC)") (class "Default")
      (node (ref "C65") (pin "2") (pinfunction "2_2") (pintype "passive"))
      (node (ref "IC4") (pin "3") (pinfunction "RFC_3") (pintype "bidirectional"))
    )
    (net (code "33") (name "Net-(IC4-VDD)") (class "Default")
      (node (ref "C51") (pin "1") (pinfunction "1_1") (pintype "passive"))
      (node (ref "C52") (pin "2") (pinfunction "2_2") (pintype "passive"))
      (node (ref "C53") (pin "2") (pinfunction "2_2") (pintype "passive"))
      (node (ref "IC4") (pin "1") (pinfunction "VDD_1") (pintype "power_in"))
      (node (ref "L8") (pin "1") (pinfunction "1_1") (pintype "passive"))
    )
    (net (code "34") (name "Net-(L7-Pad1)") (class "Default")
      (node (ref "L7") (pin "1") (pinfunction "1_1") (pintype "passive"))
      (node (ref "R46") (pin "2") (pinfunction "2_2") (pintype "passive"))
    )
    (net (code "35") (name "Net-(R19-Pad2)") (class "Default")
      (node (ref "R19") (pin "2") (pinfunction "2_2") (pintype "passive"))
      (node (ref "R34") (pin "1") (pinfunction "1_1") (pintype "passive"))
      (node (ref "R39") (pin "2") (pinfunction "2_2") (pintype "passive"))
      (node (ref "R47") (pin "2") (pinfunction "2_2") (pintype "passive"))
    )
    (net (code "36") (name "Net-(R20-Pad2)") (class "Default")
      (node (ref "R20") (pin "2") (pinfunction "2_2") (pintype "passive"))
      (node (ref "R34") (pin "2") (pinfunction "2_2") (pintype "passive"))
      (node (ref "R36") (pin "1") (pinfunction "1_1") (pintype "passive"))
      (node (ref "R40") (pin "2") (pinfunction "2_2") (pintype "passive"))
    )
    (net (code "37") (name "Net-(R22-Pad2)") (class "Default")
      (node (ref "R22") (pin "2") (pinfunction "2_2") (pintype "passive"))
      (node (ref "R36") (pin "2") (pinfunction "2_2") (pintype "passive"))
      (node (ref "R37") (pin "1") (pinfunction "1_1") (pintype "passive"))
      (node (ref "R41") (pin "2") (pinfunction "2_2") (pintype "passive"))
    )
    (net (code "38") (name "Net-(R31-Pad2)") (class "Default")
      (node (ref "R31") (pin "2") (pinfunction "2_2") (pintype "passive"))
      (node (ref "R37") (pin "2") (pinfunction "2_2") (pintype "passive"))
      (node (ref "R38") (pin "2") (pinfunction "2_2") (pintype "passive"))
      (node (ref "R42") (pin "2") (pinfunction "2_2") (pintype "passive"))
    )
    (net (code "39") (name "Net-(R47-Pad1)") (class "Default")
      (node (ref "R47") (pin "1") (pinfunction "1_1") (pintype "passive"))
      (node (ref "TR1") (pin "3") (pinfunction "P1_3") (pintype "passive"))
    )
    (net (code "40") (name "P5V0A") (class "Default")
      (node (ref "L8") (pin "2") (pinfunction "2_2") (pintype "passive"))
      (node (ref "L9") (pin "1") (pinfunction "1_1") (pintype "passive"))
    )
    (net (code "41") (name "P7V0A") (class "Default")
      (node (ref "C42") (pin "2") (pinfunction "2_2") (pintype "passive"))
      (node (ref "C43") (pin "2") (pinfunction "2_2") (pintype "passive"))
      (node (ref "R46") (pin "1") (pinfunction "1_1") (pintype "passive"))
    )
    (net (code "42") (name "unconnected-(IC4-NC-Pad4)") (class "Default")
      (node (ref "IC4") (pin "4") (pinfunction "NC_4") (pintype "passive"))
    )
    (net (code "43") (name "unconnected-(IC4-NC-Pad6)") (class "Default")
      (node (ref "IC4") (pin "6") (pinfunction "NC_6") (pintype "passive"))
    )
    (net (code "44") (name "unconnected-(IC4-NC-Pad7)") (class "Default")
      (node (ref "IC4") (pin "7") (pinfunction "NC_7") (pintype "passive"))
    )
    (net (code "45") (name "unconnected-(IC4-NC-Pad8)") (class "Default")
      (node (ref "IC4") (pin "8") (pinfunction "NC_8") (pintype "passive"))
    )
    (net (code "46") (name "unconnected-(IC4-NC-Pad13)") (class "Default")
      (node (ref "IC4") (pin "13") (pinfunction "NC_13") (pintype "passive"))
    )
    (net (code "47") (name "unconnected-(IC4-NC-Pad14)") (class "Default")
      (node (ref "IC4") (pin "14") (pinfunction "NC_14") (pintype "passive"))
    )
    (net (code "48") (name "unconnected-(IC4-NC-Pad15)") (class "Default")
      (node (ref "IC4") (pin "15") (pinfunction "NC_15") (pintype "passive"))
    )
    (net (code "49") (name "unconnected-(IC4-NC-Pad16)") (class "Default")
      (node (ref "IC4") (pin "16") (pinfunction "NC_16") (pintype "passive"))
    )
  )
)
